# EnviEye.net
KiCad netlist of a schematic drawn in EAGLE
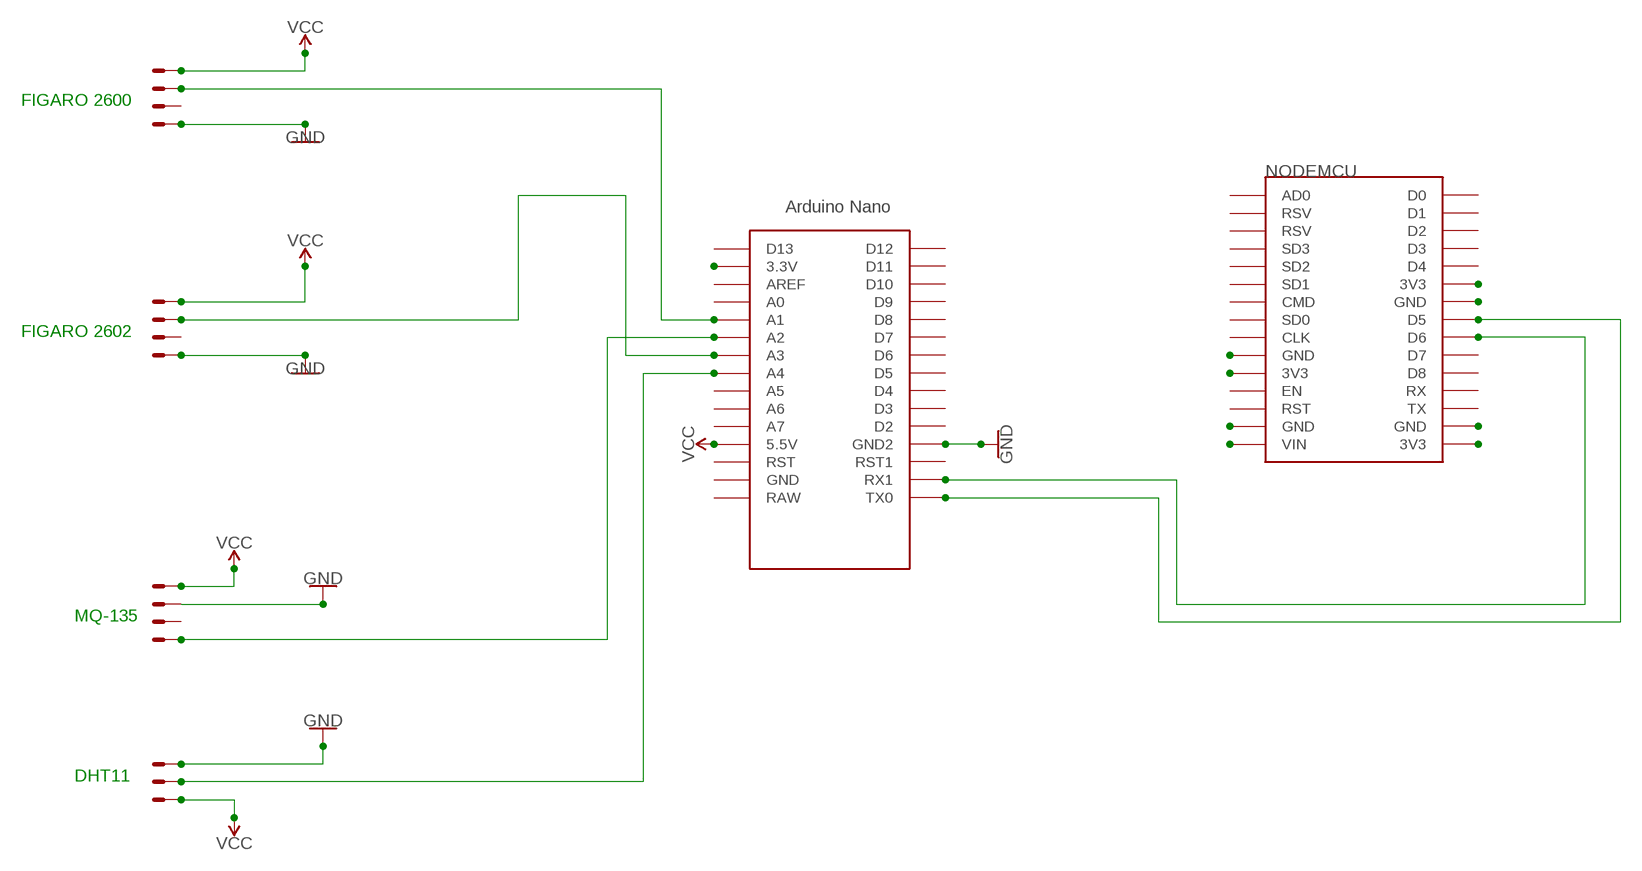
[diagram p0: schematic, sheet 1]

(export (version "E")
  (design (tool "Eeschema 10.0.6"))
  (components
    (comp (ref "DHT11")
      (value "22-23-2031")
      (footprint "eagle-import:22-23-2031")
      (fields (field (name "MF") "MOLEX"))
      (libsource (lib "eagle-import") (part "22-23-2031"))
    )
    (comp (ref "FIGARO2600")
      (value "22-23-2041")
      (footprint "eagle-import:22-23-2041")
      (fields (field (name "MF") "MOLEX"))
      (libsource (lib "eagle-import") (part "22-23-2041"))
    )
    (comp (ref "FIGARO2602")
      (value "22-23-2041")
      (footprint "eagle-import:22-23-2041")
      (fields (field (name "MF") "MOLEX"))
      (libsource (lib "eagle-import") (part "22-23-2041"))
    )
    (comp (ref "MQ-135")
      (value "22-23-2041")
      (footprint "eagle-import:22-23-2041")
      (fields (field (name "MF") "MOLEX"))
      (libsource (lib "eagle-import") (part "22-23-2041"))
    )
    (comp (ref "NODEMCU")
      (value "ESP12E_DEVKIT")
      (footprint "eagle-import:ESP12E_DEVKIT")
      (libsource (lib "eagle-import") (part "ESP12E_DEVKIT"))
    )
    (comp (ref "U$1")
      (value "NANO")
      (footprint "eagle-import:NANO")
      (libsource (lib "eagle-import") (part "NANO"))
    )
  )
  (nets
    (net (code "1") (name "GND") (class "Default")
      (node (ref "DHT11") (pin "3") (pinfunction "S_3") (pintype "passive"))
      (node (ref "FIGARO2600") (pin "4") (pinfunction "S_4") (pintype "passive"))
      (node (ref "FIGARO2602") (pin "4") (pinfunction "S_4") (pintype "passive"))
      (node (ref "MQ-135") (pin "2") (pinfunction "S_2") (pintype "passive"))
      (node (ref "U$1") (pin "GND1") (pinfunction "GND2_GND1") (pintype "bidirectional"))
    )
    (net (code "2") (name "Net-(DHT11B-S)") (class "Default")
      (node (ref "DHT11") (pin "2") (pinfunction "S_2") (pintype "passive"))
      (node (ref "U$1") (pin "A4") (pinfunction "A4_A4") (pintype "bidirectional"))
    )
    (net (code "3") (name "Net-(FIGARO2600B-S)") (class "Default")
      (node (ref "FIGARO2600") (pin "2") (pinfunction "S_2") (pintype "passive"))
      (node (ref "U$1") (pin "A3") (pinfunction "A3_A3") (pintype "bidirectional"))
    )
    (net (code "4") (name "Net-(FIGARO2602B-S)") (class "Default")
      (node (ref "FIGARO2602") (pin "2") (pinfunction "S_2") (pintype "passive"))
      (node (ref "U$1") (pin "A1") (pinfunction "A1_A1") (pintype "bidirectional"))
    )
    (net (code "5") (name "Net-(MQ-135D-S)") (class "Default")
      (node (ref "MQ-135") (pin "4") (pinfunction "S_4") (pintype "passive"))
      (node (ref "U$1") (pin "A2") (pinfunction "A2_A2") (pintype "bidirectional"))
    )
    (net (code "6") (name "Net-(NODEMCU-PadD5)") (class "Default")
      (node (ref "NODEMCU") (pin "D5") (pinfunction "D5_D5") (pintype "bidirectional"))
      (node (ref "U$1") (pin "TX0") (pinfunction "TX0_TX0") (pintype "bidirectional"))
    )
    (net (code "7") (name "Net-(NODEMCU-PadD6)") (class "Default")
      (node (ref "NODEMCU") (pin "D6") (pinfunction "D6_D6") (pintype "bidirectional"))
      (node (ref "U$1") (pin "RX1") (pinfunction "RX1_RX1") (pintype "bidirectional"))
    )
    (net (code "8") (name "VCC") (class "Default")
      (node (ref "DHT11") (pin "1") (pinfunction "S_1") (pintype "passive"))
      (node (ref "FIGARO2600") (pin "1") (pinfunction "S_1") (pintype "passive"))
      (node (ref "FIGARO2602") (pin "1") (pinfunction "S_1") (pintype "passive"))
      (node (ref "MQ-135") (pin "1") (pinfunction "S_1") (pintype "passive"))
      (node (ref "U$1") (pin "5V") (pinfunction "5.5V_5V") (pintype "bidirectional"))
    )
    (net (code "9") (name "unconnected-(FIGARO2600C-S-Pad3)") (class "Default")
      (node (ref "FIGARO2600") (pin "3") (pinfunction "S_3") (pintype "passive"))
    )
    (net (code "10") (name "unconnected-(FIGARO2602C-S-Pad3)") (class "Default")
      (node (ref "FIGARO2602") (pin "3") (pinfunction "S_3") (pintype "passive"))
    )
    (net (code "11") (name "unconnected-(MQ-135C-S-Pad3)") (class "Default")
      (node (ref "MQ-135") (pin "3") (pinfunction "S_3") (pintype "passive"))
    )
    (net (code "12") (name "unconnected-(NODEMCU-3V3-Pad3V3@0)") (class "Default")
      (node (ref "NODEMCU") (pin "3V3@0") (pinfunction "3V3_3V3@0") (pintype "bidirectional"))
    )
    (net (code "13") (name "unconnected-(NODEMCU-3V3-Pad3V3@1)") (class "Default")
      (node (ref "NODEMCU") (pin "3V3@1") (pinfunction "3V3_3V3@1") (pintype "bidirectional"))
    )
    (net (code "14") (name "unconnected-(NODEMCU-3V3-Pad3V3@2)") (class "Default")
      (node (ref "NODEMCU") (pin "3V3@2") (pinfunction "3V3_3V3@2") (pintype "bidirectional"))
    )
    (net (code "15") (name "unconnected-(NODEMCU-GND-PadGND@0)") (class "Default")
      (node (ref "NODEMCU") (pin "GND@0") (pinfunction "GND_GND@0") (pintype "bidirectional"))
    )
    (net (code "16") (name "unconnected-(NODEMCU-GND-PadGND@1)") (class "Default")
      (node (ref "NODEMCU") (pin "GND@1") (pinfunction "GND_GND@1") (pintype "bidirectional"))
    )
    (net (code "17") (name "unconnected-(NODEMCU-GND-PadGND@2)") (class "Default")
      (node (ref "NODEMCU") (pin "GND@2") (pinfunction "GND_GND@2") (pintype "bidirectional"))
    )
    (net (code "18") (name "unconnected-(NODEMCU-GND-PadGND@3)") (class "Default")
      (node (ref "NODEMCU") (pin "GND@3") (pinfunction "GND_GND@3") (pintype "bidirectional"))
    )
    (net (code "19") (name "unconnected-(NODEMCU-PadAD0)") (class "Default")
      (node (ref "NODEMCU") (pin "AD0") (pinfunction "AD0_AD0") (pintype "bidirectional"))
    )
    (net (code "20") (name "unconnected-(NODEMCU-PadCLK)") (class "Default")
      (node (ref "NODEMCU") (pin "CLK") (pinfunction "CLK_CLK") (pintype "bidirectional"))
    )
    (net (code "21") (name "unconnected-(NODEMCU-PadCMD)") (class "Default")
      (node (ref "NODEMCU") (pin "CMD") (pinfunction "CMD_CMD") (pintype "bidirectional"))
    )
    (net (code "22") (name "unconnected-(NODEMCU-PadD0)") (class "Default")
      (node (ref "NODEMCU") (pin "D0") (pinfunction "D0_D0") (pintype "bidirectional"))
    )
    (net (code "23") (name "unconnected-(NODEMCU-PadD1)") (class "Default")
      (node (ref "NODEMCU") (pin "D1") (pinfunction "D1_D1") (pintype "bidirectional"))
    )
    (net (code "24") (name "unconnected-(NODEMCU-PadD2)") (class "Default")
      (node (ref "NODEMCU") (pin "D2") (pinfunction "D2_D2") (pintype "bidirectional"))
    )
    (net (code "25") (name "unconnected-(NODEMCU-PadD3)") (class "Default")
      (node (ref "NODEMCU") (pin "D3") (pinfunction "D3_D3") (pintype "bidirectional"))
    )
    (net (code "26") (name "unconnected-(NODEMCU-PadD4)") (class "Default")
      (node (ref "NODEMCU") (pin "D4") (pinfunction "D4_D4") (pintype "bidirectional"))
    )
    (net (code "27") (name "unconnected-(NODEMCU-PadD7)") (class "Default")
      (node (ref "NODEMCU") (pin "D7") (pinfunction "D7_D7") (pintype "bidirectional"))
    )
    (net (code "28") (name "unconnected-(NODEMCU-PadD8)") (class "Default")
      (node (ref "NODEMCU") (pin "D8") (pinfunction "D8_D8") (pintype "bidirectional"))
    )
    (net (code "29") (name "unconnected-(NODEMCU-PadEN)") (class "Default")
      (node (ref "NODEMCU") (pin "EN") (pinfunction "EN_EN") (pintype "bidirectional"))
    )
    (net (code "30") (name "unconnected-(NODEMCU-PadRST)") (class "Default")
      (node (ref "NODEMCU") (pin "RST") (pinfunction "RST_RST") (pintype "bidirectional"))
    )
    (net (code "31") (name "unconnected-(NODEMCU-PadRX)") (class "Default")
      (node (ref "NODEMCU") (pin "RX") (pinfunction "RX_RX") (pintype "bidirectional"))
    )
    (net (code "32") (name "unconnected-(NODEMCU-PadSD0)") (class "Default")
      (node (ref "NODEMCU") (pin "SD0") (pinfunction "SD0_SD0") (pintype "bidirectional"))
    )
    (net (code "33") (name "unconnected-(NODEMCU-PadSD1)") (class "Default")
      (node (ref "NODEMCU") (pin "SD1") (pinfunction "SD1_SD1") (pintype "bidirectional"))
    )
    (net (code "34") (name "unconnected-(NODEMCU-PadSD2)") (class "Default")
      (node (ref "NODEMCU") (pin "SD2") (pinfunction "SD2_SD2") (pintype "bidirectional"))
    )
    (net (code "35") (name "unconnected-(NODEMCU-PadSD3)") (class "Default")
      (node (ref "NODEMCU") (pin "SD3") (pinfunction "SD3_SD3") (pintype "bidirectional"))
    )
    (net (code "36") (name "unconnected-(NODEMCU-PadTX)") (class "Default")
      (node (ref "NODEMCU") (pin "TX") (pinfunction "TX_TX") (pintype "bidirectional"))
    )
    (net (code "37") (name "unconnected-(NODEMCU-PadVIN)") (class "Default")
      (node (ref "NODEMCU") (pin "VIN") (pinfunction "VIN_VIN") (pintype "bidirectional"))
    )
    (net (code "38") (name "unconnected-(NODEMCU-RSV-PadRSV@0)") (class "Default")
      (node (ref "NODEMCU") (pin "RSV@0") (pinfunction "RSV_RSV@0") (pintype "bidirectional"))
    )
    (net (code "39") (name "unconnected-(NODEMCU-RSV-PadRSV@1)") (class "Default")
      (node (ref "NODEMCU") (pin "RSV@1") (pinfunction "RSV_RSV@1") (pintype "bidirectional"))
    )
    (net (code "40") (name "unconnected-(U$1-Pad3.3V)") (class "Default")
      (node (ref "U$1") (pin "3.3V") (pinfunction "3.3V_3.3V") (pintype "bidirectional"))
    )
    (net (code "41") (name "unconnected-(U$1-PadA0)") (class "Default")
      (node (ref "U$1") (pin "A0") (pinfunction "A0_A0") (pintype "bidirectional"))
    )
    (net (code "42") (name "unconnected-(U$1-PadA5)") (class "Default")
      (node (ref "U$1") (pin "A5") (pinfunction "A5_A5") (pintype "bidirectional"))
    )
    (net (code "43") (name "unconnected-(U$1-PadA6)") (class "Default")
      (node (ref "U$1") (pin "A6") (pinfunction "A6_A6") (pintype "bidirectional"))
    )
    (net (code "44") (name "unconnected-(U$1-PadA7)") (class "Default")
      (node (ref "U$1") (pin "A7") (pinfunction "A7_A7") (pintype "bidirectional"))
    )
    (net (code "45") (name "unconnected-(U$1-PadAREF)") (class "Default")
      (node (ref "U$1") (pin "AREF") (pinfunction "AREF_AREF") (pintype "bidirectional"))
    )
    (net (code "46") (name "unconnected-(U$1-PadD2)") (class "Default")
      (node (ref "U$1") (pin "D2") (pinfunction "D2_D2") (pintype "bidirectional"))
    )
    (net (code "47") (name "unconnected-(U$1-PadD3)") (class "Default")
      (node (ref "U$1") (pin "D3") (pinfunction "D3_D3") (pintype "bidirectional"))
    )
    (net (code "48") (name "unconnected-(U$1-PadD4)") (class "Default")
      (node (ref "U$1") (pin "D4") (pinfunction "D4_D4") (pintype "bidirectional"))
    )
    (net (code "49") (name "unconnected-(U$1-PadD5)") (class "Default")
      (node (ref "U$1") (pin "D5") (pinfunction "D5_D5") (pintype "bidirectional"))
    )
    (net (code "50") (name "unconnected-(U$1-PadD6)") (class "Default")
      (node (ref "U$1") (pin "D6") (pinfunction "D6_D6") (pintype "bidirectional"))
    )
    (net (code "51") (name "unconnected-(U$1-PadD7)") (class "Default")
      (node (ref "U$1") (pin "D7") (pinfunction "D7_D7") (pintype "bidirectional"))
    )
    (net (code "52") (name "unconnected-(U$1-PadD8)") (class "Default")
      (node (ref "U$1") (pin "D8") (pinfunction "D8_D8") (pintype "bidirectional"))
    )
    (net (code "53") (name "unconnected-(U$1-PadD9)") (class "Default")
      (node (ref "U$1") (pin "D9") (pinfunction "D9_D9") (pintype "bidirectional"))
    )
    (net (code "54") (name "unconnected-(U$1-PadD10)") (class "Default")
      (node (ref "U$1") (pin "D10") (pinfunction "D10_D10") (pintype "bidirectional"))
    )
    (net (code "55") (name "unconnected-(U$1-PadD11)") (class "Default")
      (node (ref "U$1") (pin "D11") (pinfunction "D11_D11") (pintype "bidirectional"))
    )
    (net (code "56") (name "unconnected-(U$1-PadD12)") (class "Default")
      (node (ref "U$1") (pin "D12") (pinfunction "D12_D12") (pintype "bidirectional"))
    )
    (net (code "57") (name "unconnected-(U$1-PadD13)") (class "Default")
      (node (ref "U$1") (pin "D13") (pinfunction "D13_D13") (pintype "bidirectional"))
    )
    (net (code "58") (name "unconnected-(U$1-PadGND)") (class "Default")
      (node (ref "U$1") (pin "GND") (pinfunction "GND_GND") (pintype "bidirectional"))
    )
    (net (code "59") (name "unconnected-(U$1-PadICSP1)") (class "Default")
      (node (ref "U$1") (pin "ICSP1") (pinfunction "ICSP1_ICSP1") (pintype "bidirectional"))
    )
    (net (code "60") (name "unconnected-(U$1-PadICSP2)") (class "Default")
      (node (ref "U$1") (pin "ICSP2") (pinfunction "ICSP2_ICSP2") (pintype "bidirectional"))
    )
    (net (code "61") (name "unconnected-(U$1-PadICSP3)") (class "Default")
      (node (ref "U$1") (pin "ICSP3") (pinfunction "ICSP3_ICSP3") (pintype "bidirectional"))
    )
    (net (code "62") (name "unconnected-(U$1-PadICSP4)") (class "Default")
      (node (ref "U$1") (pin "ICSP4") (pinfunction "ICSP4_ICSP4") (pintype "bidirectional"))
    )
    (net (code "63") (name "unconnected-(U$1-PadICSP5)") (class "Default")
      (node (ref "U$1") (pin "ICSP5") (pinfunction "ICSP5_ICSP5") (pintype "bidirectional"))
    )
    (net (code "64") (name "unconnected-(U$1-PadICSP6)") (class "Default")
      (node (ref "U$1") (pin "ICSP6") (pinfunction "ICSP6_ICSP6") (pintype "bidirectional"))
    )
    (net (code "65") (name "unconnected-(U$1-PadRAW)") (class "Default")
      (node (ref "U$1") (pin "RAW") (pinfunction "RAW_RAW") (pintype "bidirectional"))
    )
    (net (code "66") (name "unconnected-(U$1-PadRST)") (class "Default")
      (node (ref "U$1") (pin "RST") (pinfunction "RST_RST") (pintype "bidirectional"))
    )
    (net (code "67") (name "unconnected-(U$1-PadRST1)") (class "Default")
      (node (ref "U$1") (pin "RST1") (pinfunction "RST1_RST1") (pintype "bidirectional"))
    )
  )
)
